# PLC_RaspberryPi.net
KiCad netlist of a schematic drawn in Altium Designer
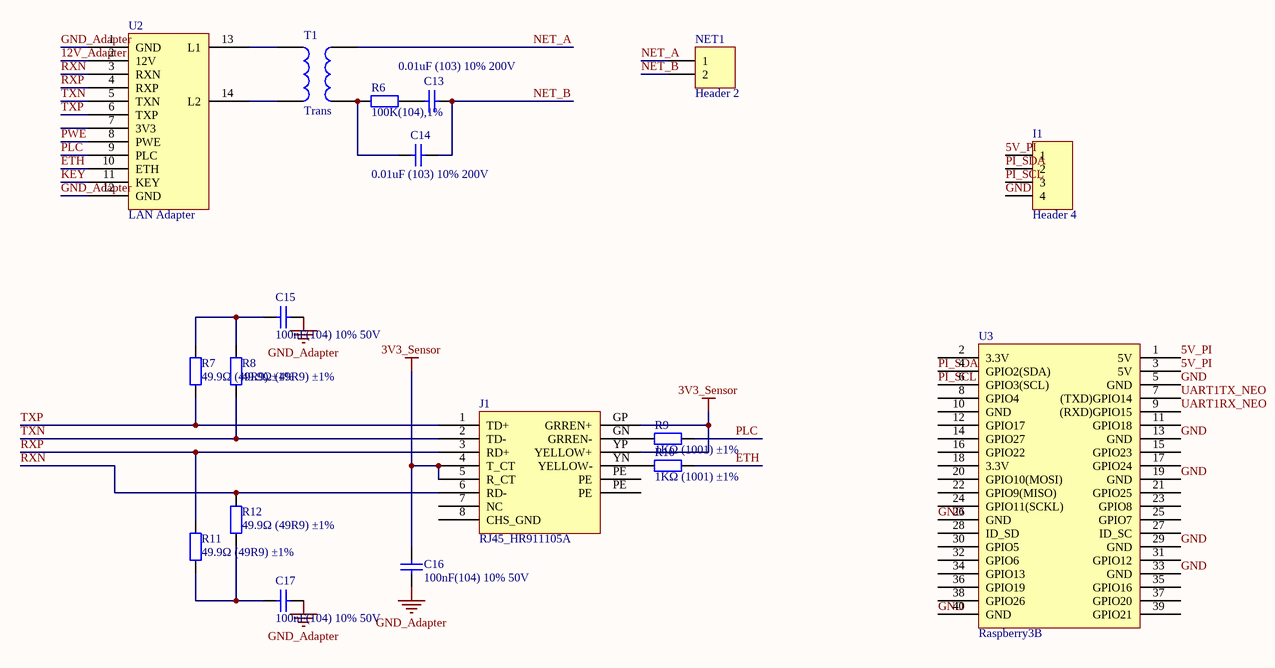
[diagram p0: PLC_RaspberryPi.SchDoc]

(export (version "E")
  (design (tool "Eeschema 10.0.6"))
  (components
    (comp (ref "C13")
      (value "0.01uF (103) 10% 200V")
      (footprint "1206_C")
      (description "Capacitor")
      (fields (field (name "PUBLISHER") "Altium Limited"))
      (libsource (lib "STM32F103C8T6(原理图库)") (part "Cap"))
    )
    (comp (ref "C14")
      (value "0.01uF (103) 10% 200V")
      (footprint "1206_C")
      (description "Capacitor")
      (fields (field (name "PUBLISHER") "Altium Limited"))
      (libsource (lib "STM32F103C8T6(原理图库)") (part "Cap"))
    )
    (comp (ref "C15")
      (value "100nF(104) 10% 50V")
      (footprint "0603_C")
      (description "贴片电容")
      (libsource (lib "Miscellaneous Devices LC") (part "0805 100nF(104) 10% 50V"))
    )
    (comp (ref "C16")
      (value "100nF(104) 10% 50V")
      (footprint "0603_C")
      (description "贴片电容")
      (libsource (lib "Miscellaneous Devices LC") (part "0805 100nF(104) 10% 50V"))
    )
    (comp (ref "C17")
      (value "100nF(104) 10% 50V")
      (footprint "0603_C")
      (description "贴片电容")
      (libsource (lib "Miscellaneous Devices LC") (part "0805 100nF(104) 10% 50V"))
    )
    (comp (ref "I1")
      (value "Header 4")
      (footprint "XH2.54_4P")
      (description "Header, 4-Pin")
      (fields (field (name "PUBLISHER") "Altium Limited"))
      (libsource (lib "Miscellaneous Connectors") (part "Header 4"))
    )
    (comp (ref "J1")
      (value "RJ45_HR911105A")
      (footprint "RJ45_3")
      (libsource (lib "RJ45") (part "RJ45_HR911105A"))
    )
    (comp (ref "NET1")
      (value "Header 2")
      (footprint "XH2.54_2P")
      (description "Header, 2-Pin")
      (fields (field (name "PUBLISHER") "Altium Limited"))
      (libsource (lib "Miscellaneous Connectors") (part "Header 2"))
    )
    (comp (ref "R6")
      (value "100K(104),1%")
      (footprint "1206_R")
      (description "Resistor")
      (fields (field (name "PUBLISHER") "Altium Limited"))
      (libsource (lib "STM32F103C8T6(原理图库)") (part "Res2"))
    )
    (comp (ref "R7")
      (value "49.9Ω (49R9) ±1%")
      (footprint "0603_R")
      (description "贴片电阻")
      (libsource (lib "Miscellaneous Devices LC") (part "0805 49.9Ω (49R9) 1%"))
    )
    (comp (ref "R8")
      (value "49.9Ω (49R9) ±1%")
      (footprint "0603_R")
      (description "贴片电阻")
      (libsource (lib "Miscellaneous Devices LC") (part "0805 49.9Ω (49R9) 1%"))
    )
    (comp (ref "R9")
      (value "1KΩ (1001) ±1%")
      (footprint "0603_R")
      (description "贴片电阻")
      (libsource (lib "Miscellaneous Devices LC") (part "0603 1KΩ (1001) 1%"))
    )
    (comp (ref "R10")
      (value "1KΩ (1001) ±1%")
      (footprint "0603_R")
      (description "贴片电阻")
      (libsource (lib "Miscellaneous Devices LC") (part "0603 1KΩ (1001) 1%"))
    )
    (comp (ref "R11")
      (value "49.9Ω (49R9) ±1%")
      (footprint "0603_R")
      (description "贴片电阻")
      (libsource (lib "Miscellaneous Devices LC") (part "0805 49.9Ω (49R9) 1%"))
    )
    (comp (ref "R12")
      (value "49.9Ω (49R9) ±1%")
      (footprint "0603_R")
      (description "贴片电阻")
      (libsource (lib "Miscellaneous Devices LC") (part "0805 49.9Ω (49R9) 1%"))
    )
    (comp (ref "T1")
      (value "Trans")
      (footprint "SW-80")
      (description "Transformer")
      (fields (field (name "PUBLISHER") "Altium Limited"))
      (libsource (lib "Miscellaneous Devices") (part "Trans"))
    )
    (comp (ref "U2")
      (value "LAN Adapter")
      (footprint "LAN Adapter")
      (libsource (lib "Adapter") (part "LAN Adapter"))
    )
    (comp (ref "U3")
      (value "Raspberry3B")
      (footprint "HDR2X20")
      (libsource (lib "Raspberry") (part "Raspberry3B"))
    )
  )
  (nets
    (net (code "1") (name "/5V_PI") (class "Default")
      (node (ref "I1") (pin "1") (pinfunction "1_1") (pintype "passive"))
      (node (ref "U3") (pin "1") (pinfunction "5V_1") (pintype "passive"))
      (node (ref "U3") (pin "3") (pinfunction "5V_3") (pintype "passive"))
    )
    (net (code "2") (name "/12V_Adapter") (class "Default")
      (node (ref "U2") (pin "2") (pinfunction "12V_2") (pintype "passive"))
    )
    (net (code "3") (name "/ETH") (class "Default")
      (node (ref "R10") (pin "2") (pinfunction "2_2") (pintype "passive"))
      (node (ref "U2") (pin "10") (pinfunction "ETH_10") (pintype "passive"))
    )
    (net (code "4") (name "/GND") (class "Default")
      (node (ref "I1") (pin "4") (pinfunction "4_4") (pintype "passive"))
      (node (ref "U3") (pin "13") (pinfunction "GND_13") (pintype "passive"))
      (node (ref "U3") (pin "19") (pinfunction "GND_19") (pintype "passive"))
      (node (ref "U3") (pin "26") (pinfunction "GND_26") (pintype "passive"))
      (node (ref "U3") (pin "29") (pinfunction "GND_29") (pintype "passive"))
      (node (ref "U3") (pin "33") (pinfunction "GND_33") (pintype "passive"))
      (node (ref "U3") (pin "40") (pinfunction "GND_40") (pintype "passive"))
      (node (ref "U3") (pin "5") (pinfunction "GND_5") (pintype "passive"))
    )
    (net (code "5") (name "/KEY") (class "Default")
      (node (ref "U2") (pin "11") (pinfunction "KEY_11") (pintype "passive"))
    )
    (net (code "6") (name "/NET_A") (class "Default")
      (node (ref "NET1") (pin "1") (pinfunction "1_1") (pintype "passive"))
      (node (ref "T1") (pin "3") (pinfunction "3_3") (pintype "passive"))
    )
    (net (code "7") (name "/NET_B") (class "Default")
      (node (ref "C13") (pin "1") (pinfunction "1_1") (pintype "passive"))
      (node (ref "C14") (pin "1") (pinfunction "1_1") (pintype "passive"))
      (node (ref "NET1") (pin "2") (pinfunction "2_2") (pintype "passive"))
    )
    (net (code "8") (name "/PI_SCL") (class "Default")
      (node (ref "I1") (pin "3") (pinfunction "3_3") (pintype "passive"))
      (node (ref "U3") (pin "6") (pinfunction "GPIO3(SCL)_6") (pintype "passive"))
    )
    (net (code "9") (name "/PI_SDA") (class "Default")
      (node (ref "I1") (pin "2") (pinfunction "2_2") (pintype "passive"))
      (node (ref "U3") (pin "4") (pinfunction "GPIO2(SDA)_4") (pintype "passive"))
    )
    (net (code "10") (name "/PLC") (class "Default")
      (node (ref "R9") (pin "2") (pinfunction "2_2") (pintype "passive"))
      (node (ref "U2") (pin "9") (pinfunction "PLC_9") (pintype "passive"))
    )
    (net (code "11") (name "/PWE") (class "Default")
      (node (ref "U2") (pin "8") (pinfunction "PWE_8") (pintype "passive"))
    )
    (net (code "12") (name "/RXN") (class "Default")
      (node (ref "J1") (pin "6") (pinfunction "RD-_6") (pintype "passive"))
      (node (ref "R12") (pin "2") (pinfunction "2_2") (pintype "passive"))
      (node (ref "U2") (pin "3") (pinfunction "RXN_3") (pintype "passive"))
    )
    (net (code "13") (name "/RXP") (class "Default")
      (node (ref "J1") (pin "3") (pinfunction "RD+_3") (pintype "passive"))
      (node (ref "R11") (pin "2") (pinfunction "2_2") (pintype "passive"))
      (node (ref "U2") (pin "4") (pinfunction "RXP_4") (pintype "passive"))
    )
    (net (code "14") (name "/TXN") (class "Default")
      (node (ref "J1") (pin "2") (pinfunction "TD-_2") (pintype "passive"))
      (node (ref "R8") (pin "1") (pinfunction "1_1") (pintype "passive"))
      (node (ref "U2") (pin "5") (pinfunction "TXN_5") (pintype "passive"))
    )
    (net (code "15") (name "/TXP") (class "Default")
      (node (ref "J1") (pin "1") (pinfunction "TD+_1") (pintype "passive"))
      (node (ref "R7") (pin "1") (pinfunction "1_1") (pintype "passive"))
      (node (ref "U2") (pin "6") (pinfunction "TXP_6") (pintype "passive"))
    )
    (net (code "16") (name "/UART1RX_NEO") (class "Default")
      (node (ref "U3") (pin "9") (pinfunction "(RXD)GPIO15_9") (pintype "passive"))
    )
    (net (code "17") (name "/UART1TX_NEO") (class "Default")
      (node (ref "U3") (pin "7") (pinfunction "(TXD)GPIO14_7") (pintype "passive"))
    )
    (net (code "18") (name "3V3_Sensor") (class "Default")
      (node (ref "C16") (pin "2") (pinfunction "2_2") (pintype "passive"))
      (node (ref "J1") (pin "4") (pinfunction "T_CT_4") (pintype "passive"))
      (node (ref "J1") (pin "5") (pinfunction "R_CT_5") (pintype "passive"))
      (node (ref "J1") (pin "GP") (pinfunction "GRREN+_GP") (pintype "passive"))
      (node (ref "J1") (pin "YP") (pinfunction "YELLOW+_YP") (pintype "passive"))
    )
    (net (code "19") (name "GND_Adapter") (class "Default")
      (node (ref "C15") (pin "1") (pinfunction "1_1") (pintype "passive"))
      (node (ref "C16") (pin "1") (pinfunction "1_1") (pintype "passive"))
      (node (ref "C17") (pin "1") (pinfunction "1_1") (pintype "passive"))
      (node (ref "U2") (pin "1") (pinfunction "GND_1") (pintype "passive"))
      (node (ref "U2") (pin "12") (pinfunction "GND_12") (pintype "passive"))
    )
    (net (code "20") (name "Net-(C13-Pad2)") (class "Default")
      (node (ref "C13") (pin "2") (pinfunction "2_2") (pintype "passive"))
      (node (ref "R6") (pin "2") (pinfunction "2_2") (pintype "passive"))
    )
    (net (code "21") (name "Net-(C14-Pad2)") (class "Default")
      (node (ref "C14") (pin "2") (pinfunction "2_2") (pintype "passive"))
      (node (ref "R6") (pin "1") (pinfunction "1_1") (pintype "passive"))
      (node (ref "T1") (pin "4") (pinfunction "4_4") (pintype "passive"))
    )
    (net (code "22") (name "Net-(C15-Pad2)") (class "Default")
      (node (ref "C15") (pin "2") (pinfunction "2_2") (pintype "passive"))
      (node (ref "R7") (pin "2") (pinfunction "2_2") (pintype "passive"))
      (node (ref "R8") (pin "2") (pinfunction "2_2") (pintype "passive"))
    )
    (net (code "23") (name "Net-(C17-Pad2)") (class "Default")
      (node (ref "C17") (pin "2") (pinfunction "2_2") (pintype "passive"))
      (node (ref "R11") (pin "1") (pinfunction "1_1") (pintype "passive"))
      (node (ref "R12") (pin "1") (pinfunction "1_1") (pintype "passive"))
    )
    (net (code "24") (name "Net-(J1-GRREN-)") (class "Default")
      (node (ref "J1") (pin "GN") (pinfunction "GRREN-_GN") (pintype "passive"))
      (node (ref "R9") (pin "1") (pinfunction "1_1") (pintype "passive"))
    )
    (net (code "25") (name "Net-(J1-YELLOW-)") (class "Default")
      (node (ref "J1") (pin "YN") (pinfunction "YELLOW-_YN") (pintype "passive"))
      (node (ref "R10") (pin "1") (pinfunction "1_1") (pintype "passive"))
    )
    (net (code "26") (name "Net-(U2-L1)") (class "Default")
      (node (ref "T1") (pin "1") (pinfunction "1_1") (pintype "passive"))
      (node (ref "U2") (pin "13") (pinfunction "L1_13") (pintype "passive"))
    )
    (net (code "27") (name "Net-(U2-L2)") (class "Default")
      (node (ref "T1") (pin "2") (pinfunction "2_2") (pintype "passive"))
      (node (ref "U2") (pin "14") (pinfunction "L2_14") (pintype "passive"))
    )
    (net (code "28") (name "unconnected-(J1-CHS_GND-Pad8)") (class "Default")
      (node (ref "J1") (pin "8") (pinfunction "CHS_GND_8") (pintype "passive"))
    )
    (net (code "29") (name "unconnected-(J1-NC-Pad7)") (class "Default")
      (node (ref "J1") (pin "7") (pinfunction "NC_7") (pintype "passive"))
    )
    (net (code "30") (name "unconnected-(J1-PadPE)") (class "Default")
      (node (ref "J1") (pin "PE") (pinfunction "PE_PE") (pintype "passive"))
    )
    (net (code "31") (name "unconnected-(J1-PadPE)_1") (class "Default")
      (node (ref "J1") (pin "PE") (pinfunction "PE_PE") (pintype "passive"))
    )
    (net (code "32") (name "unconnected-(U2-3V3-Pad7)") (class "Default")
      (node (ref "U2") (pin "7") (pinfunction "3V3_7") (pintype "passive"))
    )
    (net (code "33") (name "unconnected-(U3-3.3V-Pad2)") (class "Default")
      (node (ref "U3") (pin "2") (pinfunction "3.3V_2") (pintype "passive"))
    )
    (net (code "34") (name "unconnected-(U3-3.3V-Pad18)") (class "Default")
      (node (ref "U3") (pin "18") (pinfunction "3.3V_18") (pintype "passive"))
    )
    (net (code "35") (name "unconnected-(U3-GND-Pad10)") (class "Default")
      (node (ref "U3") (pin "10") (pinfunction "GND_10") (pintype "passive"))
    )
    (net (code "36") (name "unconnected-(U3-GPIO4-Pad8)") (class "Default")
      (node (ref "U3") (pin "8") (pinfunction "GPIO4_8") (pintype "passive"))
    )
    (net (code "37") (name "unconnected-(U3-GPIO5-Pad30)") (class "Default")
      (node (ref "U3") (pin "30") (pinfunction "GPIO5_30") (pintype "passive"))
    )
    (net (code "38") (name "unconnected-(U3-GPIO6-Pad32)") (class "Default")
      (node (ref "U3") (pin "32") (pinfunction "GPIO6_32") (pintype "passive"))
    )
    (net (code "39") (name "unconnected-(U3-GPIO7-Pad25)") (class "Default")
      (node (ref "U3") (pin "25") (pinfunction "GPIO7_25") (pintype "passive"))
    )
    (net (code "40") (name "unconnected-(U3-GPIO8-Pad23)") (class "Default")
      (node (ref "U3") (pin "23") (pinfunction "GPIO8_23") (pintype "passive"))
    )
    (net (code "41") (name "unconnected-(U3-GPIO9(MISO)-Pad22)") (class "Default")
      (node (ref "U3") (pin "22") (pinfunction "GPIO9(MISO)_22") (pintype "passive"))
    )
    (net (code "42") (name "unconnected-(U3-GPIO10(MOSI)-Pad20)") (class "Default")
      (node (ref "U3") (pin "20") (pinfunction "GPIO10(MOSI)_20") (pintype "passive"))
    )
    (net (code "43") (name "unconnected-(U3-GPIO11(SCKL)-Pad24)") (class "Default")
      (node (ref "U3") (pin "24") (pinfunction "GPIO11(SCKL)_24") (pintype "passive"))
    )
    (net (code "44") (name "unconnected-(U3-GPIO12-Pad31)") (class "Default")
      (node (ref "U3") (pin "31") (pinfunction "GPIO12_31") (pintype "passive"))
    )
    (net (code "45") (name "unconnected-(U3-GPIO13-Pad34)") (class "Default")
      (node (ref "U3") (pin "34") (pinfunction "GPIO13_34") (pintype "passive"))
    )
    (net (code "46") (name "unconnected-(U3-GPIO16-Pad35)") (class "Default")
      (node (ref "U3") (pin "35") (pinfunction "GPIO16_35") (pintype "passive"))
    )
    (net (code "47") (name "unconnected-(U3-GPIO17-Pad12)") (class "Default")
      (node (ref "U3") (pin "12") (pinfunction "GPIO17_12") (pintype "passive"))
    )
    (net (code "48") (name "unconnected-(U3-GPIO18-Pad11)") (class "Default")
      (node (ref "U3") (pin "11") (pinfunction "GPIO18_11") (pintype "passive"))
    )
    (net (code "49") (name "unconnected-(U3-GPIO19-Pad36)") (class "Default")
      (node (ref "U3") (pin "36") (pinfunction "GPIO19_36") (pintype "passive"))
    )
    (net (code "50") (name "unconnected-(U3-GPIO20-Pad37)") (class "Default")
      (node (ref "U3") (pin "37") (pinfunction "GPIO20_37") (pintype "passive"))
    )
    (net (code "51") (name "unconnected-(U3-GPIO21-Pad39)") (class "Default")
      (node (ref "U3") (pin "39") (pinfunction "GPIO21_39") (pintype "passive"))
    )
    (net (code "52") (name "unconnected-(U3-GPIO22-Pad16)") (class "Default")
      (node (ref "U3") (pin "16") (pinfunction "GPIO22_16") (pintype "passive"))
    )
    (net (code "53") (name "unconnected-(U3-GPIO23-Pad15)") (class "Default")
      (node (ref "U3") (pin "15") (pinfunction "GPIO23_15") (pintype "passive"))
    )
    (net (code "54") (name "unconnected-(U3-GPIO24-Pad17)") (class "Default")
      (node (ref "U3") (pin "17") (pinfunction "GPIO24_17") (pintype "passive"))
    )
    (net (code "55") (name "unconnected-(U3-GPIO25-Pad21)") (class "Default")
      (node (ref "U3") (pin "21") (pinfunction "GPIO25_21") (pintype "passive"))
    )
    (net (code "56") (name "unconnected-(U3-GPIO26-Pad38)") (class "Default")
      (node (ref "U3") (pin "38") (pinfunction "GPIO26_38") (pintype "passive"))
    )
    (net (code "57") (name "unconnected-(U3-GPIO27-Pad14)") (class "Default")
      (node (ref "U3") (pin "14") (pinfunction "GPIO27_14") (pintype "passive"))
    )
    (net (code "58") (name "unconnected-(U3-ID_SC-Pad27)") (class "Default")
      (node (ref "U3") (pin "27") (pinfunction "ID_SC_27") (pintype "passive"))
    )
    (net (code "59") (name "unconnected-(U3-ID_SD-Pad28)") (class "Default")
      (node (ref "U3") (pin "28") (pinfunction "ID_SD_28") (pintype "passive"))
    )
  )
)
